# Impedance.net
KiCad netlist of a schematic drawn in EAGLE
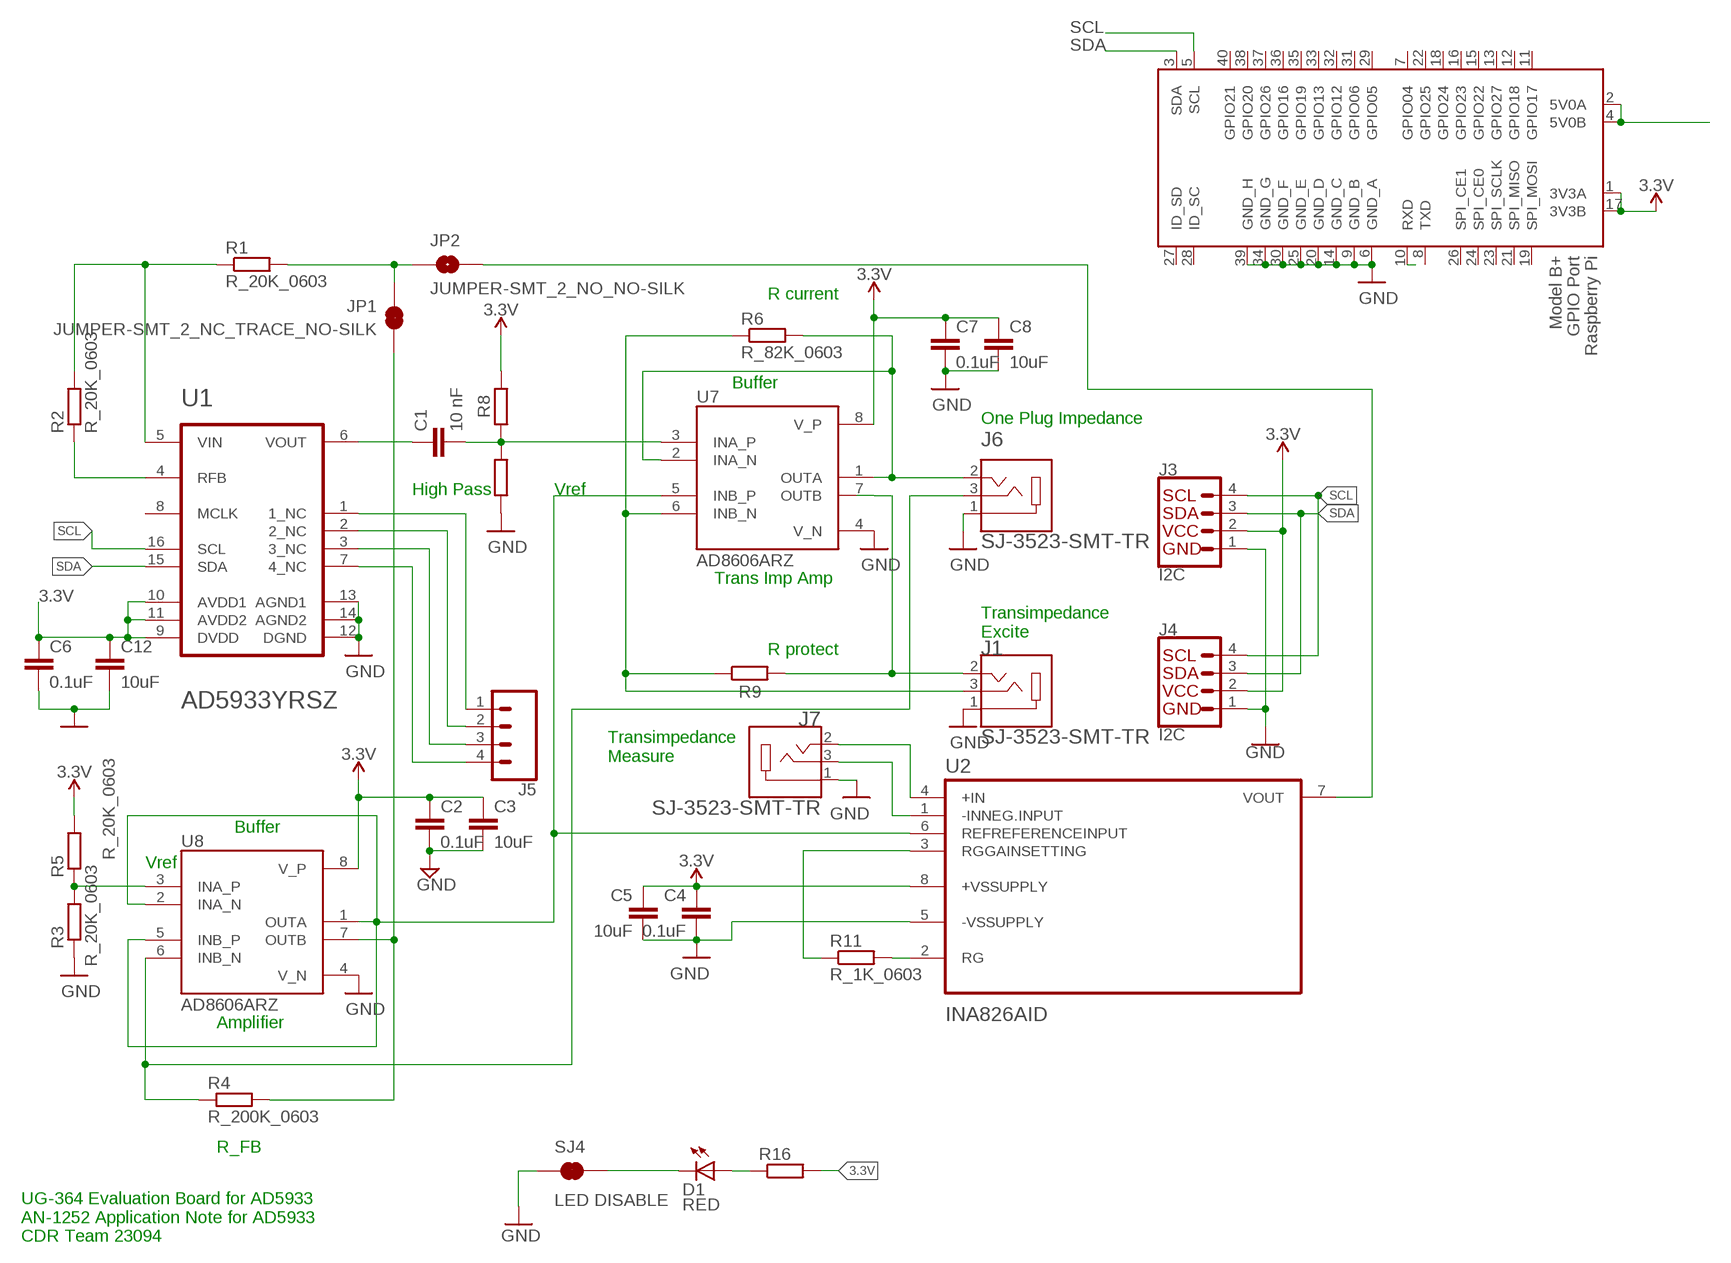
[diagram p0: schematic, sheet 1]

(export (version "E")
  (design (tool "Eeschema 10.0.6"))
  (components
    (comp (ref "C1")
      (value "10 nF")
      (footprint "eagle-import:0603")
      (libsource (lib "eagle-import") (part "3.3NF-0603-100V-10%"))
    )
    (comp (ref "C2")
      (value "0.1uF")
      (footprint "eagle-import:0603")
      (libsource (lib "eagle-import") (part "0.1UF-0603-25V-(+80/-20%)"))
    )
    (comp (ref "C3")
      (value "10uF")
      (footprint "eagle-import:0603")
      (libsource (lib "eagle-import") (part "10UF-0603-6.3V-20%"))
    )
    (comp (ref "C4")
      (value "0.1uF")
      (footprint "eagle-import:0603")
      (libsource (lib "eagle-import") (part "0.1UF-0603-25V-(+80/-20%)"))
    )
    (comp (ref "C5")
      (value "10uF")
      (footprint "eagle-import:0603")
      (libsource (lib "eagle-import") (part "10UF-0603-6.3V-20%"))
    )
    (comp (ref "C6")
      (value "0.1uF")
      (footprint "eagle-import:0603")
      (libsource (lib "eagle-import") (part "0.1UF-0603-25V-(+80/-20%)"))
    )
    (comp (ref "C7")
      (value "0.1uF")
      (footprint "eagle-import:0603")
      (libsource (lib "eagle-import") (part "0.1UF-0603-25V-(+80/-20%)"))
    )
    (comp (ref "C8")
      (value "10uF")
      (footprint "eagle-import:0603")
      (libsource (lib "eagle-import") (part "10UF-0603-6.3V-20%"))
    )
    (comp (ref "C12")
      (value "10uF")
      (footprint "eagle-import:0603")
      (libsource (lib "eagle-import") (part "10UF-0603-6.3V-20%"))
    )
    (comp (ref "D1")
      (value "RED")
      (footprint "eagle-import:LED-0603")
      (libsource (lib "eagle-import") (part "LED-RED0603"))
    )
    (comp (ref "J1")
      (value "SJ-3523-SMT-TR")
      (footprint "eagle-import:CUI_SJ-3523-SMT-TR")
      (fields (field (name "MF") "CUI Devices"))
      (libsource (lib "eagle-import") (part "SJ-3523-SMT-TR"))
    )
    (comp (ref "J3")
      (value "I2C")
      (footprint "eagle-import:JST04_1MM_RA")
      (libsource (lib "eagle-import") (part "QWIIC_CONNECTORJS-1MM"))
    )
    (comp (ref "J4")
      (value "I2C")
      (footprint "eagle-import:JST04_1MM_RA")
      (libsource (lib "eagle-import") (part "QWIIC_CONNECTORJS-1MM"))
    )
    (comp (ref "J5")
      (value "CONN_04")
      (footprint "eagle-import:1X04")
      (libsource (lib "eagle-import") (part "CONN_04"))
    )
    (comp (ref "J6")
      (value "SJ-3523-SMT-TR")
      (footprint "eagle-import:CUI_SJ-3523-SMT-TR")
      (fields (field (name "MF") "CUI Devices"))
      (libsource (lib "eagle-import") (part "SJ-3523-SMT-TR"))
    )
    (comp (ref "J7")
      (value "SJ-3523-SMT-TR")
      (footprint "eagle-import:CUI_SJ-3523-SMT-TR")
      (fields (field (name "MF") "CUI Devices"))
      (libsource (lib "eagle-import") (part "SJ-3523-SMT-TR"))
    )
    (comp (ref "JP1")
      (value "JUMPER-SMT_2_NC_TRACE_NO-SILK")
      (footprint "eagle-import:SMT-JUMPER_2_NC_TRACE_NO-SILK")
      (libsource (lib "eagle-import") (part "JUMPER-SMT_2_NC_TRACE_NO-SILK"))
    )
    (comp (ref "JP2")
      (value "JUMPER-SMT_2_NO_NO-SILK")
      (footprint "eagle-import:SMT-JUMPER_2_NO_NO-SILK")
      (libsource (lib "eagle-import") (part "JUMPER-SMT_2_NO_NO-SILK"))
    )
    (comp (ref "R1")
      (value "R_20K_0603")
      (footprint "eagle-import:R0603")
      (fields (field (name "LCSC_PART") "C4184"))
      (libsource (lib "eagle-import") (part "R__060320K"))
    )
    (comp (ref "R2")
      (value "R_20K_0603")
      (footprint "eagle-import:R0603")
      (fields (field (name "LCSC_PART") "C4184"))
      (libsource (lib "eagle-import") (part "R__060320K"))
    )
    (comp (ref "R3")
      (value "R_20K_0603")
      (footprint "eagle-import:R0603")
      (fields (field (name "LCSC_PART") "C4184"))
      (libsource (lib "eagle-import") (part "R__060320K"))
    )
    (comp (ref "R4")
      (value "R_200K_0603")
      (footprint "eagle-import:R0603")
      (fields (field (name "LCSC_PART") "C25811"))
      (libsource (lib "eagle-import") (part "R__0603200K"))
    )
    (comp (ref "R5")
      (value "R_20K_0603")
      (footprint "eagle-import:R0603")
      (fields (field (name "LCSC_PART") "C4184"))
      (libsource (lib "eagle-import") (part "R__060320K"))
    )
    (comp (ref "R6")
      (value "R_82K_0603")
      (footprint "eagle-import:R0603")
      (fields (field (name "LCSC_PART") "C23254"))
      (libsource (lib "eagle-import") (part "R__060382K"))
    )
    (comp (ref "R7")
      (value "100 kO")
      (footprint "eagle-import:R0603")
      (fields (field (name "LCSC_PART") "C25803"))
      (libsource (lib "eagle-import") (part "R__0603100K"))
    )
    (comp (ref "R8")
      (value "100 kO")
      (footprint "eagle-import:R0603")
      (fields (field (name "LCSC_PART") "C25803"))
      (libsource (lib "eagle-import") (part "R__0603100K"))
    )
    (comp (ref "R9")
      (value "1 MO")
      (footprint "eagle-import:R0603")
      (fields (field (name "LCSC_PART") "C23254"))
      (libsource (lib "eagle-import") (part "R__060382K"))
    )
    (comp (ref "R11")
      (value "R_1K_0603")
      (footprint "eagle-import:R0603")
      (fields (field (name "LCSC_PART") "C21190"))
      (libsource (lib "eagle-import") (part "R__06031K"))
    )
    (comp (ref "R16")
      (value "R__0603")
      (footprint "eagle-import:R0603")
      (fields (field (name "LCSC_PART") "C21190"))
      (libsource (lib "eagle-import") (part "R__06031K"))
    )
    (comp (ref "SJ4")
      (value "LED DISABLE")
      (footprint "eagle-import:SMT-JUMPER_2_NC_TRACE_NO-SILK")
      (libsource (lib "eagle-import") (part "JUMPER-SMT_2_NC_TRACE_NO-SILK"))
    )
    (comp (ref "U1")
      (value "ANALOG_DEVICES_AD5933YRSZANALOG_DEVICES_AD5933YRSZ_0_0")
      (footprint "eagle-import:ANALOG_DEVICES_AD5933YRSZ_0")
      (fields (field (name "MF") "Analog Devices") (field (name "MPN") "AD5933YRSZ"))
      (libsource (lib "eagle-import") (part "ANALOG_DEVICES_AD5933YRSZANALOG_DEVICES_AD5933YRSZ_0_0"))
    )
    (comp (ref "U2")
      (value "INA826AID")
      (footprint "eagle-import:SOIC127P599X175-8N")
      (fields (field (name "MF") "Texas Instruments"))
      (libsource (lib "eagle-import") (part "INA826AID"))
    )
    (comp (ref "U7")
      (value "AD8606ARZ")
      (footprint "eagle-import:SOIC127P600X175-8N")
      (fields (field (name "MF") "Analog Devices"))
      (libsource (lib "eagle-import") (part "AD8606ARZ"))
    )
    (comp (ref "U8")
      (value "AD8606ARZ")
      (footprint "eagle-import:SOIC127P600X175-8N")
      (fields (field (name "MF") "Analog Devices"))
      (libsource (lib "eagle-import") (part "AD8606ARZ"))
    )
    (comp (ref "X1")
      (value "RASPI_BOARD_B+#_H")
      (footprint "eagle-import:RASPI_BOARD_B+HAT")
      (libsource (lib "eagle-import") (part "RASPI_BOARD_B+#_H"))
    )
  )
  (nets
    (net (code "1") (name "3.3V") (class "Default")
      (node (ref "C12") (pin "1") (pinfunction "1_1") (pintype "passive"))
      (node (ref "C2") (pin "1") (pinfunction "1_1") (pintype "passive"))
      (node (ref "C3") (pin "1") (pinfunction "1_1") (pintype "passive"))
      (node (ref "C4") (pin "1") (pinfunction "1_1") (pintype "passive"))
      (node (ref "C5") (pin "1") (pinfunction "1_1") (pintype "passive"))
      (node (ref "C6") (pin "1") (pinfunction "1_1") (pintype "passive"))
      (node (ref "C7") (pin "1") (pinfunction "1_1") (pintype "passive"))
      (node (ref "C8") (pin "1") (pinfunction "1_1") (pintype "passive"))
      (node (ref "J3") (pin "2") (pinfunction "2_2") (pintype "power_in"))
      (node (ref "J4") (pin "2") (pinfunction "2_2") (pintype "power_in"))
      (node (ref "R16") (pin "2") (pinfunction "2_2") (pintype "passive"))
      (node (ref "R5") (pin "2") (pinfunction "2_2") (pintype "passive"))
      (node (ref "R8") (pin "2") (pinfunction "2_2") (pintype "passive"))
      (node (ref "U1") (pin "10") (pinfunction "AVDD1_10") (pintype "power_in"))
      (node (ref "U1") (pin "11") (pinfunction "AVDD2_11") (pintype "power_in"))
      (node (ref "U1") (pin "9") (pinfunction "DVDD_9") (pintype "power_in"))
      (node (ref "U2") (pin "8") (pinfunction "+VSSUPPLY_8") (pintype "bidirectional"))
      (node (ref "U7") (pin "8") (pinfunction "V_P_8") (pintype "power_in"))
      (node (ref "U8") (pin "8") (pinfunction "V_P_8") (pintype "power_in"))
      (node (ref "X1") (pin "1") (pinfunction "3V3A_1") (pintype "power_in"))
      (node (ref "X1") (pin "17") (pinfunction "3V3B_17") (pintype "power_in"))
    )
    (net (code "2") (name "GND") (class "Default")
      (node (ref "C12") (pin "2") (pinfunction "2_2") (pintype "passive"))
      (node (ref "C2") (pin "2") (pinfunction "2_2") (pintype "passive"))
      (node (ref "C3") (pin "2") (pinfunction "2_2") (pintype "passive"))
      (node (ref "C4") (pin "2") (pinfunction "2_2") (pintype "passive"))
      (node (ref "C5") (pin "2") (pinfunction "2_2") (pintype "passive"))
      (node (ref "C6") (pin "2") (pinfunction "2_2") (pintype "passive"))
      (node (ref "C7") (pin "2") (pinfunction "2_2") (pintype "passive"))
      (node (ref "C8") (pin "2") (pinfunction "2_2") (pintype "passive"))
      (node (ref "J1") (pin "1") (pinfunction "1_1") (pintype "passive"))
      (node (ref "J3") (pin "1") (pinfunction "1_1") (pintype "power_in"))
      (node (ref "J4") (pin "1") (pinfunction "1_1") (pintype "power_in"))
      (node (ref "J6") (pin "1") (pinfunction "1_1") (pintype "passive"))
      (node (ref "J7") (pin "1") (pinfunction "1_1") (pintype "passive"))
      (node (ref "R3") (pin "1") (pinfunction "1_1") (pintype "passive"))
      (node (ref "R7") (pin "1") (pinfunction "1_1") (pintype "passive"))
      (node (ref "SJ4") (pin "1") (pinfunction "1_1") (pintype "passive"))
      (node (ref "U1") (pin "12") (pinfunction "DGND_12") (pintype "power_in"))
      (node (ref "U1") (pin "13") (pinfunction "AGND1_13") (pintype "power_in"))
      (node (ref "U1") (pin "14") (pinfunction "AGND2_14") (pintype "power_in"))
      (node (ref "U2") (pin "5") (pinfunction "-VSSUPPLY_5") (pintype "bidirectional"))
      (node (ref "U7") (pin "4") (pinfunction "V_N_4") (pintype "power_in"))
      (node (ref "U8") (pin "4") (pinfunction "V_N_4") (pintype "power_in"))
      (node (ref "X1") (pin "14") (pinfunction "GND_C_14") (pintype "power_in"))
      (node (ref "X1") (pin "20") (pinfunction "GND_D_20") (pintype "power_in"))
      (node (ref "X1") (pin "25") (pinfunction "GND_E_25") (pintype "power_in"))
      (node (ref "X1") (pin "30") (pinfunction "GND_F_30") (pintype "power_in"))
      (node (ref "X1") (pin "34") (pinfunction "GND_G_34") (pintype "power_in"))
      (node (ref "X1") (pin "39") (pinfunction "GND_H_39") (pintype "power_in"))
      (node (ref "X1") (pin "6") (pinfunction "GND_A_6") (pintype "power_in"))
      (node (ref "X1") (pin "9") (pinfunction "GND_B_9") (pintype "power_in"))
    )
    (net (code "3") (name "Net-(D1-PadA)") (class "Default")
      (node (ref "D1") (pin "A") (pinfunction "A_A") (pintype "passive"))
      (node (ref "R16") (pin "1") (pinfunction "1_1") (pintype "passive"))
    )
    (net (code "4") (name "Net-(D1-PadC)") (class "Default")
      (node (ref "D1") (pin "C") (pinfunction "C_C") (pintype "passive"))
      (node (ref "SJ4") (pin "2") (pinfunction "2_2") (pintype "passive"))
    )
    (net (code "5") (name "Net-(JP1-Pad2)") (class "Default")
      (node (ref "JP1") (pin "2") (pinfunction "2_2") (pintype "passive"))
      (node (ref "JP2") (pin "1") (pinfunction "1_1") (pintype "passive"))
      (node (ref "R1") (pin "2") (pinfunction "2_2") (pintype "passive"))
    )
    (net (code "6") (name "Net-(U1-1_NC)") (class "Default")
      (node (ref "J5") (pin "1") (pinfunction "1_1") (pintype "passive"))
      (node (ref "U1") (pin "1") (pinfunction "1_NC_1") (pintype "passive"))
    )
    (net (code "7") (name "Net-(U1-2_NC)") (class "Default")
      (node (ref "J5") (pin "2") (pinfunction "2_2") (pintype "passive"))
      (node (ref "U1") (pin "2") (pinfunction "2_NC_2") (pintype "passive"))
    )
    (net (code "8") (name "Net-(U1-3_NC)") (class "Default")
      (node (ref "J5") (pin "3") (pinfunction "3_3") (pintype "passive"))
      (node (ref "U1") (pin "3") (pinfunction "3_NC_3") (pintype "passive"))
    )
    (net (code "9") (name "Net-(U1-4_NC)") (class "Default")
      (node (ref "J5") (pin "4") (pinfunction "4_4") (pintype "passive"))
      (node (ref "U1") (pin "7") (pinfunction "4_NC_7") (pintype "passive"))
    )
    (net (code "10") (name "Net-(U1-RFB)") (class "Default")
      (node (ref "R2") (pin "1") (pinfunction "1_1") (pintype "passive"))
      (node (ref "U1") (pin "4") (pinfunction "RFB_4") (pintype "input"))
    )
    (net (code "11") (name "Net-(U1-VIN)") (class "Default")
      (node (ref "R1") (pin "1") (pinfunction "1_1") (pintype "passive"))
      (node (ref "R2") (pin "2") (pinfunction "2_2") (pintype "passive"))
      (node (ref "U1") (pin "5") (pinfunction "VIN_5") (pintype "input"))
    )
    (net (code "12") (name "Net-(U1-VOUT)") (class "Default")
      (node (ref "C1") (pin "1") (pinfunction "1_1") (pintype "passive"))
      (node (ref "U1") (pin "6") (pinfunction "VOUT_6") (pintype "output"))
    )
    (net (code "13") (name "Net-(U2-+IN)") (class "Default")
      (node (ref "J7") (pin "2") (pinfunction "2_2") (pintype "passive"))
      (node (ref "U2") (pin "4") (pinfunction "+IN_4") (pintype "input"))
    )
    (net (code "14") (name "Net-(U2--INNEG.INPUT)") (class "Default")
      (node (ref "J7") (pin "3") (pinfunction "3_3") (pintype "passive"))
      (node (ref "U2") (pin "1") (pinfunction "-INNEG.INPUT_1") (pintype "input"))
    )
    (net (code "15") (name "Net-(U2-REFREFERENCEINPUT)") (class "Default")
      (node (ref "U2") (pin "6") (pinfunction "REFREFERENCEINPUT_6") (pintype "input"))
      (node (ref "U7") (pin "5") (pinfunction "INB_P_5") (pintype "input"))
      (node (ref "U8") (pin "1") (pinfunction "OUTA_1") (pintype "input"))
      (node (ref "U8") (pin "2") (pinfunction "INA_N_2") (pintype "input"))
      (node (ref "U8") (pin "5") (pinfunction "INB_P_5") (pintype "input"))
    )
    (net (code "16") (name "Net-(U2-RG)") (class "Default")
      (node (ref "R11") (pin "2") (pinfunction "2_2") (pintype "passive"))
      (node (ref "U2") (pin "2") (pinfunction "RG_2") (pintype "bidirectional"))
    )
    (net (code "17") (name "Net-(U2-RGGAINSETTING)") (class "Default")
      (node (ref "R11") (pin "1") (pinfunction "1_1") (pintype "passive"))
      (node (ref "U2") (pin "3") (pinfunction "RGGAINSETTING_3") (pintype "input"))
    )
    (net (code "18") (name "Net-(U2-VOUT)") (class "Default")
      (node (ref "JP2") (pin "2") (pinfunction "2_2") (pintype "passive"))
      (node (ref "U2") (pin "7") (pinfunction "VOUT_7") (pintype "output"))
    )
    (net (code "19") (name "Net-(U7-INA_N)") (class "Default")
      (node (ref "J6") (pin "2") (pinfunction "2_2") (pintype "passive"))
      (node (ref "R6") (pin "2") (pinfunction "2_2") (pintype "passive"))
      (node (ref "U7") (pin "1") (pinfunction "OUTA_1") (pintype "input"))
      (node (ref "U7") (pin "2") (pinfunction "INA_N_2") (pintype "input"))
    )
    (net (code "20") (name "Net-(U7-INA_P)") (class "Default")
      (node (ref "C1") (pin "2") (pinfunction "2_2") (pintype "passive"))
      (node (ref "R7") (pin "2") (pinfunction "2_2") (pintype "passive"))
      (node (ref "R8") (pin "1") (pinfunction "1_1") (pintype "passive"))
      (node (ref "U7") (pin "3") (pinfunction "INA_P_3") (pintype "input"))
    )
    (net (code "21") (name "Net-(U7-INB_N)") (class "Default")
      (node (ref "J1") (pin "3") (pinfunction "3_3") (pintype "passive"))
      (node (ref "R6") (pin "1") (pinfunction "1_1") (pintype "passive"))
      (node (ref "R9") (pin "1") (pinfunction "1_1") (pintype "passive"))
      (node (ref "U7") (pin "6") (pinfunction "INB_N_6") (pintype "input"))
    )
    (net (code "22") (name "Net-(U7-OUTB)") (class "Default")
      (node (ref "J1") (pin "2") (pinfunction "2_2") (pintype "passive"))
      (node (ref "R9") (pin "2") (pinfunction "2_2") (pintype "passive"))
      (node (ref "U7") (pin "7") (pinfunction "OUTB_7") (pintype "input"))
    )
    (net (code "23") (name "Net-(U8-INA_P)") (class "Default")
      (node (ref "R3") (pin "2") (pinfunction "2_2") (pintype "passive"))
      (node (ref "R5") (pin "1") (pinfunction "1_1") (pintype "passive"))
      (node (ref "U8") (pin "3") (pinfunction "INA_P_3") (pintype "input"))
    )
    (net (code "24") (name "Net-(U8-INB_N)") (class "Default")
      (node (ref "J6") (pin "3") (pinfunction "3_3") (pintype "passive"))
      (node (ref "R4") (pin "1") (pinfunction "1_1") (pintype "passive"))
      (node (ref "U8") (pin "6") (pinfunction "INB_N_6") (pintype "input"))
    )
    (net (code "25") (name "Net-(U8-OUTB)") (class "Default")
      (node (ref "JP1") (pin "1") (pinfunction "1_1") (pintype "passive"))
      (node (ref "R4") (pin "2") (pinfunction "2_2") (pintype "passive"))
      (node (ref "U8") (pin "7") (pinfunction "OUTB_7") (pintype "input"))
    )
    (net (code "26") (name "Net-(X1-5V0A)") (class "Default")
      (node (ref "X1") (pin "2") (pinfunction "5V0A_2") (pintype "power_in"))
      (node (ref "X1") (pin "4") (pinfunction "5V0B_4") (pintype "power_in"))
    )
    (net (code "27") (name "SCL") (class "Default")
      (node (ref "J3") (pin "4") (pinfunction "4_4") (pintype "passive"))
      (node (ref "J4") (pin "4") (pinfunction "4_4") (pintype "passive"))
      (node (ref "U1") (pin "16") (pinfunction "SCL_16") (pintype "input"))
      (node (ref "X1") (pin "5") (pinfunction "SCL_5") (pintype "bidirectional"))
    )
    (net (code "28") (name "SDA") (class "Default")
      (node (ref "J3") (pin "3") (pinfunction "3_3") (pintype "passive"))
      (node (ref "J4") (pin "3") (pinfunction "3_3") (pintype "passive"))
      (node (ref "U1") (pin "15") (pinfunction "SDA_15") (pintype "bidirectional"))
      (node (ref "X1") (pin "3") (pinfunction "SDA_3") (pintype "bidirectional"))
    )
    (net (code "29") (name "unconnected-(U1-MCLK-Pad8)") (class "Default")
      (node (ref "U1") (pin "8") (pinfunction "MCLK_8") (pintype "input"))
    )
    (net (code "30") (name "unconnected-(X1-GPIO04-Pad7)") (class "Default")
      (node (ref "X1") (pin "7") (pinfunction "GPIO04_7") (pintype "bidirectional"))
    )
    (net (code "31") (name "unconnected-(X1-GPIO05-Pad29)") (class "Default")
      (node (ref "X1") (pin "29") (pinfunction "GPIO05_29") (pintype "no_connect"))
    )
    (net (code "32") (name "unconnected-(X1-GPIO06-Pad31)") (class "Default")
      (node (ref "X1") (pin "31") (pinfunction "GPIO06_31") (pintype "no_connect"))
    )
    (net (code "33") (name "unconnected-(X1-GPIO12-Pad32)") (class "Default")
      (node (ref "X1") (pin "32") (pinfunction "GPIO12_32") (pintype "no_connect"))
    )
    (net (code "34") (name "unconnected-(X1-GPIO13-Pad33)") (class "Default")
      (node (ref "X1") (pin "33") (pinfunction "GPIO13_33") (pintype "no_connect"))
    )
    (net (code "35") (name "unconnected-(X1-GPIO16-Pad36)") (class "Default")
      (node (ref "X1") (pin "36") (pinfunction "GPIO16_36") (pintype "no_connect"))
    )
    (net (code "36") (name "unconnected-(X1-GPIO17-Pad11)") (class "Default")
      (node (ref "X1") (pin "11") (pinfunction "GPIO17_11") (pintype "bidirectional"))
    )
    (net (code "37") (name "unconnected-(X1-GPIO18-Pad12)") (class "Default")
      (node (ref "X1") (pin "12") (pinfunction "GPIO18_12") (pintype "bidirectional"))
    )
    (net (code "38") (name "unconnected-(X1-GPIO19-Pad35)") (class "Default")
      (node (ref "X1") (pin "35") (pinfunction "GPIO19_35") (pintype "no_connect"))
    )
    (net (code "39") (name "unconnected-(X1-GPIO20-Pad38)") (class "Default")
      (node (ref "X1") (pin "38") (pinfunction "GPIO20_38") (pintype "no_connect"))
    )
    (net (code "40") (name "unconnected-(X1-GPIO21-Pad40)") (class "Default")
      (node (ref "X1") (pin "40") (pinfunction "GPIO21_40") (pintype "no_connect"))
    )
    (net (code "41") (name "unconnected-(X1-GPIO22-Pad15)") (class "Default")
      (node (ref "X1") (pin "15") (pinfunction "GPIO22_15") (pintype "bidirectional"))
    )
    (net (code "42") (name "unconnected-(X1-GPIO23-Pad16)") (class "Default")
      (node (ref "X1") (pin "16") (pinfunction "GPIO23_16") (pintype "bidirectional"))
    )
    (net (code "43") (name "unconnected-(X1-GPIO24-Pad18)") (class "Default")
      (node (ref "X1") (pin "18") (pinfunction "GPIO24_18") (pintype "bidirectional"))
    )
    (net (code "44") (name "unconnected-(X1-GPIO25-Pad22)") (class "Default")
      (node (ref "X1") (pin "22") (pinfunction "GPIO25_22") (pintype "bidirectional"))
    )
    (net (code "45") (name "unconnected-(X1-GPIO26-Pad37)") (class "Default")
      (node (ref "X1") (pin "37") (pinfunction "GPIO26_37") (pintype "no_connect"))
    )
    (net (code "46") (name "unconnected-(X1-GPIO27-Pad13)") (class "Default")
      (node (ref "X1") (pin "13") (pinfunction "GPIO27_13") (pintype "bidirectional"))
    )
    (net (code "47") (name "unconnected-(X1-ID_SC-Pad28)") (class "Default")
      (node (ref "X1") (pin "28") (pinfunction "ID_SC_28") (pintype "no_connect"))
    )
    (net (code "48") (name "unconnected-(X1-ID_SD-Pad27)") (class "Default")
      (node (ref "X1") (pin "27") (pinfunction "ID_SD_27") (pintype "no_connect"))
    )
    (net (code "49") (name "unconnected-(X1-RXD-Pad10)") (class "Default")
      (node (ref "X1") (pin "10") (pinfunction "RXD_10") (pintype "bidirectional"))
    )
    (net (code "50") (name "unconnected-(X1-SPI_CE0-Pad24)") (class "Default")
      (node (ref "X1") (pin "24") (pinfunction "SPI_CE0_24") (pintype "bidirectional"))
    )
    (net (code "51") (name "unconnected-(X1-SPI_CE1-Pad26)") (class "Default")
      (node (ref "X1") (pin "26") (pinfunction "SPI_CE1_26") (pintype "bidirectional"))
    )
    (net (code "52") (name "unconnected-(X1-SPI_MISO-Pad21)") (class "Default")
      (node (ref "X1") (pin "21") (pinfunction "SPI_MISO_21") (pintype "bidirectional"))
    )
    (net (code "53") (name "unconnected-(X1-SPI_MOSI-Pad19)") (class "Default")
      (node (ref "X1") (pin "19") (pinfunction "SPI_MOSI_19") (pintype "bidirectional"))
    )
    (net (code "54") (name "unconnected-(X1-SPI_SCLK-Pad23)") (class "Default")
      (node (ref "X1") (pin "23") (pinfunction "SPI_SCLK_23") (pintype "bidirectional"))
    )
    (net (code "55") (name "unconnected-(X1-TXD-Pad8)") (class "Default")
      (node (ref "X1") (pin "8") (pinfunction "TXD_8") (pintype "bidirectional"))
    )
  )
)
